# main.net
KiCad netlist of a schematic drawn in EAGLE
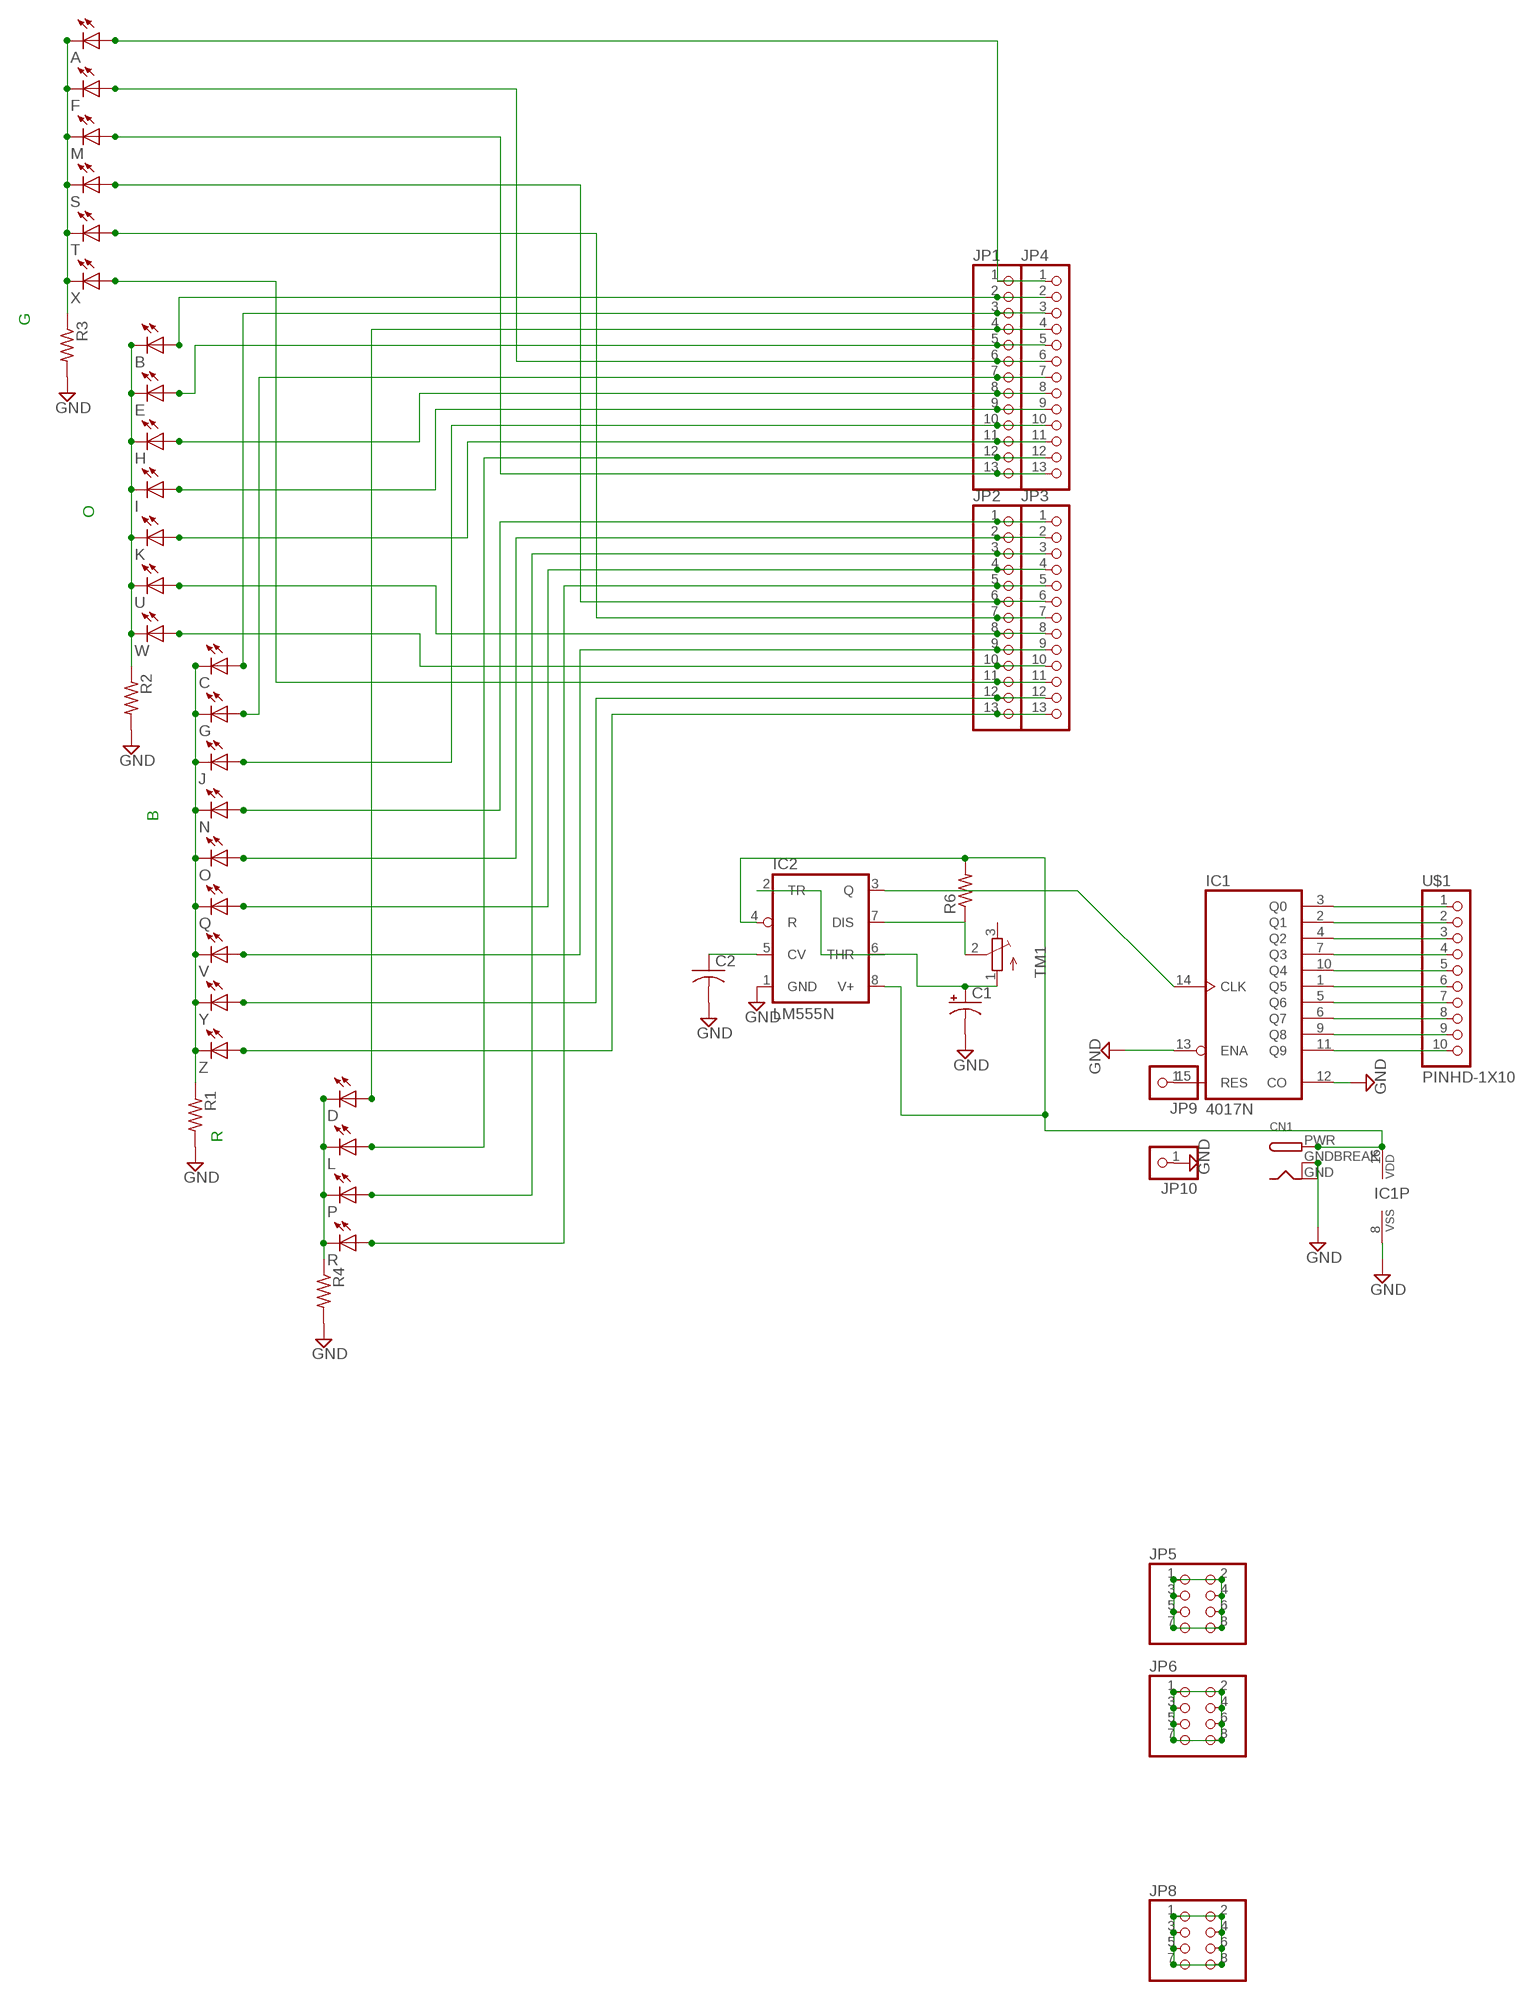
[diagram p0: schematic, sheet 1]

(export (version "E")
  (design (tool "Eeschema 10.0.6"))
  (components
    (comp (ref "A")
      (value "LED3MM")
      (footprint "eagle-import:LED3MM")
      (libsource (lib "eagle-import") (part "LED3MM"))
    )
    (comp (ref "B")
      (value "LED3MM")
      (footprint "eagle-import:LED3MM")
      (libsource (lib "eagle-import") (part "LED3MM"))
    )
    (comp (ref "C")
      (value "LED3MM")
      (footprint "eagle-import:LED3MM")
      (libsource (lib "eagle-import") (part "LED3MM"))
    )
    (comp (ref "C1")
      (value "CPOL-USE3.5-10")
      (footprint "eagle-import:E3,5-10")
      (libsource (lib "eagle-import") (part "CPOL-USE3.5-10"))
    )
    (comp (ref "C2")
      (value "C-US025-024X044")
      (footprint "eagle-import:C025-024X044")
      (libsource (lib "eagle-import") (part "C-US025-024X044"))
    )
    (comp (ref "CN1")
      (value "DCBARRELPTH")
      (footprint "eagle-import:DCJACK_2MM_PTH")
      (libsource (lib "eagle-import") (part "DCBARRELPTH"))
    )
    (comp (ref "D")
      (value "LED3MM")
      (footprint "eagle-import:LED3MM")
      (libsource (lib "eagle-import") (part "LED3MM"))
    )
    (comp (ref "E")
      (value "LED3MM")
      (footprint "eagle-import:LED3MM")
      (libsource (lib "eagle-import") (part "LED3MM"))
    )
    (comp (ref "F")
      (value "LED3MM")
      (footprint "eagle-import:LED3MM")
      (libsource (lib "eagle-import") (part "LED3MM"))
    )
    (comp (ref "G")
      (value "LED3MM")
      (footprint "eagle-import:LED3MM")
      (libsource (lib "eagle-import") (part "LED3MM"))
    )
    (comp (ref "H")
      (value "LED3MM")
      (footprint "eagle-import:LED3MM")
      (libsource (lib "eagle-import") (part "LED3MM"))
    )
    (comp (ref "I")
      (value "LED3MM")
      (footprint "eagle-import:LED3MM")
      (libsource (lib "eagle-import") (part "LED3MM"))
    )
    (comp (ref "IC1")
      (value "4017N")
      (footprint "eagle-import:DIL16")
      (libsource (lib "eagle-import") (part "4017N"))
    )
    (comp (ref "IC2")
      (value "LM555N")
      (footprint "eagle-import:DIL08")
      (libsource (lib "eagle-import") (part "555NLM"))
    )
    (comp (ref "J")
      (value "LED3MM")
      (footprint "eagle-import:LED3MM")
      (libsource (lib "eagle-import") (part "LED3MM"))
    )
    (comp (ref "JP1")
      (value "PINHD-1X13")
      (footprint "eagle-import:1X13")
      (libsource (lib "eagle-import") (part "PINHD-1X13"))
    )
    (comp (ref "JP2")
      (value "PINHD-1X13")
      (footprint "eagle-import:1X13")
      (libsource (lib "eagle-import") (part "PINHD-1X13"))
    )
    (comp (ref "JP3")
      (value "PINHD-1X13")
      (footprint "eagle-import:1X13")
      (libsource (lib "eagle-import") (part "PINHD-1X13"))
    )
    (comp (ref "JP4")
      (value "PINHD-1X13")
      (footprint "eagle-import:1X13")
      (libsource (lib "eagle-import") (part "PINHD-1X13"))
    )
    (comp (ref "JP5")
      (value "PINHD-2X4")
      (footprint "eagle-import:2X04")
      (libsource (lib "eagle-import") (part "PINHD-2X4"))
    )
    (comp (ref "JP6")
      (value "PINHD-2X4")
      (footprint "eagle-import:2X04")
      (libsource (lib "eagle-import") (part "PINHD-2X4"))
    )
    (comp (ref "JP8")
      (value "PINHD-2X4")
      (footprint "eagle-import:2X04")
      (libsource (lib "eagle-import") (part "PINHD-2X4"))
    )
    (comp (ref "JP9")
      (value "PINHD-1X1")
      (footprint "eagle-import:1X01")
      (libsource (lib "eagle-import") (part "PINHD-1X1"))
    )
    (comp (ref "JP10")
      (value "PINHD-1X1")
      (footprint "eagle-import:1X01")
      (libsource (lib "eagle-import") (part "PINHD-1X1"))
    )
    (comp (ref "K")
      (value "LED3MM")
      (footprint "eagle-import:LED3MM")
      (libsource (lib "eagle-import") (part "LED3MM"))
    )
    (comp (ref "L")
      (value "LED3MM")
      (footprint "eagle-import:LED3MM")
      (libsource (lib "eagle-import") (part "LED3MM"))
    )
    (comp (ref "M")
      (value "LED3MM")
      (footprint "eagle-import:LED3MM")
      (libsource (lib "eagle-import") (part "LED3MM"))
    )
    (comp (ref "N")
      (value "LED3MM")
      (footprint "eagle-import:LED3MM")
      (libsource (lib "eagle-import") (part "LED3MM"))
    )
    (comp (ref "O")
      (value "LED3MM")
      (footprint "eagle-import:LED3MM")
      (libsource (lib "eagle-import") (part "LED3MM"))
    )
    (comp (ref "P")
      (value "LED3MM")
      (footprint "eagle-import:LED3MM")
      (libsource (lib "eagle-import") (part "LED3MM"))
    )
    (comp (ref "Q")
      (value "LED3MM")
      (footprint "eagle-import:LED3MM")
      (libsource (lib "eagle-import") (part "LED3MM"))
    )
    (comp (ref "R")
      (value "LED3MM")
      (footprint "eagle-import:LED3MM")
      (libsource (lib "eagle-import") (part "LED3MM"))
    )
    (comp (ref "R1")
      (value "R-US_0207/7")
      (footprint "eagle-import:0207_7")
      (libsource (lib "eagle-import") (part "R-US_0207/7"))
    )
    (comp (ref "R2")
      (value "R-US_0207/7")
      (footprint "eagle-import:0207_7")
      (libsource (lib "eagle-import") (part "R-US_0207/7"))
    )
    (comp (ref "R3")
      (value "R-US_0207/7")
      (footprint "eagle-import:0207_7")
      (libsource (lib "eagle-import") (part "R-US_0207/7"))
    )
    (comp (ref "R4")
      (value "R-US_0207/7")
      (footprint "eagle-import:0207_7")
      (libsource (lib "eagle-import") (part "R-US_0207/7"))
    )
    (comp (ref "R6")
      (value "R-US_0207/7")
      (footprint "eagle-import:0207_7")
      (libsource (lib "eagle-import") (part "R-US_0207/7"))
    )
    (comp (ref "S")
      (value "LED3MM")
      (footprint "eagle-import:LED3MM")
      (libsource (lib "eagle-import") (part "LED3MM"))
    )
    (comp (ref "T")
      (value "LED3MM")
      (footprint "eagle-import:LED3MM")
      (libsource (lib "eagle-import") (part "LED3MM"))
    )
    (comp (ref "TM1")
      (value "TRIMPOT3386")
      (footprint "eagle-import:TRIM-3386")
      (libsource (lib "eagle-import") (part "TRIMPOT3386"))
    )
    (comp (ref "U")
      (value "LED3MM")
      (footprint "eagle-import:LED3MM")
      (libsource (lib "eagle-import") (part "LED3MM"))
    )
    (comp (ref "U$1")
      (value "PINHD-1X10")
      (footprint "eagle-import:1X10-BIG")
      (libsource (lib "eagle-import") (part "PINHD-1X10"))
    )
    (comp (ref "V")
      (value "LED3MM")
      (footprint "eagle-import:LED3MM")
      (libsource (lib "eagle-import") (part "LED3MM"))
    )
    (comp (ref "W")
      (value "LED3MM")
      (footprint "eagle-import:LED3MM")
      (libsource (lib "eagle-import") (part "LED3MM"))
    )
    (comp (ref "X")
      (value "LED3MM")
      (footprint "eagle-import:LED3MM")
      (libsource (lib "eagle-import") (part "LED3MM"))
    )
    (comp (ref "Y")
      (value "LED3MM")
      (footprint "eagle-import:LED3MM")
      (libsource (lib "eagle-import") (part "LED3MM"))
    )
    (comp (ref "Z")
      (value "LED3MM")
      (footprint "eagle-import:LED3MM")
      (libsource (lib "eagle-import") (part "LED3MM"))
    )
  )
  (nets
    (net (code "1") (name "GND") (class "Default")
      (node (ref "C1") (pin "-") (pinfunction "-_-") (pintype "passive"))
      (node (ref "C2") (pin "2") (pinfunction "2_2") (pintype "passive"))
      (node (ref "CN1") (pin "GND") (pinfunction "GND_GND") (pintype "power_in"))
      (node (ref "CN1") (pin "GNDBREAK") (pinfunction "GNDBREAK_GNDBREAK") (pintype "power_in"))
      (node (ref "IC1") (pin "12") (pinfunction "CO_12") (pintype "output"))
      (node (ref "IC1") (pin "13") (pinfunction "ENA_13") (pintype "input"))
      (node (ref "IC1") (pin "8") (pinfunction "VSS_8") (pintype "power_in"))
      (node (ref "IC2") (pin "1") (pinfunction "GND_1") (pintype "power_in"))
      (node (ref "JP10") (pin "1") (pinfunction "1_1") (pintype "passive"))
      (node (ref "R1") (pin "2") (pinfunction "2_2") (pintype "passive"))
      (node (ref "R2") (pin "2") (pinfunction "2_2") (pintype "passive"))
      (node (ref "R3") (pin "2") (pinfunction "2_2") (pintype "passive"))
      (node (ref "R4") (pin "2") (pinfunction "2_2") (pintype "passive"))
    )
    (net (code "2") (name "Net-(A-C)") (class "Default")
      (node (ref "A") (pin "K") (pinfunction "C_K") (pintype "passive"))
      (node (ref "F") (pin "K") (pinfunction "C_K") (pintype "passive"))
      (node (ref "M") (pin "K") (pinfunction "C_K") (pintype "passive"))
      (node (ref "R3") (pin "1") (pinfunction "1_1") (pintype "passive"))
      (node (ref "S") (pin "K") (pinfunction "C_K") (pintype "passive"))
      (node (ref "T") (pin "K") (pinfunction "C_K") (pintype "passive"))
      (node (ref "X") (pin "K") (pinfunction "C_K") (pintype "passive"))
    )
    (net (code "3") (name "Net-(A-PadA)") (class "Default")
      (node (ref "A") (pin "A") (pinfunction "A_A") (pintype "passive"))
      (node (ref "JP1") (pin "1") (pinfunction "1_1") (pintype "passive"))
      (node (ref "JP4") (pin "1") (pinfunction "1_1") (pintype "passive"))
    )
    (net (code "4") (name "Net-(B-C)") (class "Default")
      (node (ref "B") (pin "K") (pinfunction "C_K") (pintype "passive"))
      (node (ref "E") (pin "K") (pinfunction "C_K") (pintype "passive"))
      (node (ref "H") (pin "K") (pinfunction "C_K") (pintype "passive"))
      (node (ref "I") (pin "K") (pinfunction "C_K") (pintype "passive"))
      (node (ref "K") (pin "K") (pinfunction "C_K") (pintype "passive"))
      (node (ref "R2") (pin "1") (pinfunction "1_1") (pintype "passive"))
      (node (ref "U") (pin "K") (pinfunction "C_K") (pintype "passive"))
      (node (ref "W") (pin "K") (pinfunction "C_K") (pintype "passive"))
    )
    (net (code "5") (name "Net-(B-PadA)") (class "Default")
      (node (ref "B") (pin "A") (pinfunction "A_A") (pintype "passive"))
      (node (ref "JP1") (pin "2") (pinfunction "2_2") (pintype "passive"))
      (node (ref "JP4") (pin "2") (pinfunction "2_2") (pintype "passive"))
    )
    (net (code "6") (name "Net-(C-C)") (class "Default")
      (node (ref "C") (pin "K") (pinfunction "C_K") (pintype "passive"))
      (node (ref "G") (pin "K") (pinfunction "C_K") (pintype "passive"))
      (node (ref "J") (pin "K") (pinfunction "C_K") (pintype "passive"))
      (node (ref "N") (pin "K") (pinfunction "C_K") (pintype "passive"))
      (node (ref "O") (pin "K") (pinfunction "C_K") (pintype "passive"))
      (node (ref "Q") (pin "K") (pinfunction "C_K") (pintype "passive"))
      (node (ref "R1") (pin "1") (pinfunction "1_1") (pintype "passive"))
      (node (ref "V") (pin "K") (pinfunction "C_K") (pintype "passive"))
      (node (ref "Y") (pin "K") (pinfunction "C_K") (pintype "passive"))
      (node (ref "Z") (pin "K") (pinfunction "C_K") (pintype "passive"))
    )
    (net (code "7") (name "Net-(C-PadA)") (class "Default")
      (node (ref "C") (pin "A") (pinfunction "A_A") (pintype "passive"))
      (node (ref "JP1") (pin "3") (pinfunction "3_3") (pintype "passive"))
      (node (ref "JP4") (pin "3") (pinfunction "3_3") (pintype "passive"))
    )
    (net (code "8") (name "Net-(D-C)") (class "Default")
      (node (ref "D") (pin "K") (pinfunction "C_K") (pintype "passive"))
      (node (ref "L") (pin "K") (pinfunction "C_K") (pintype "passive"))
      (node (ref "P") (pin "K") (pinfunction "C_K") (pintype "passive"))
      (node (ref "R") (pin "K") (pinfunction "C_K") (pintype "passive"))
      (node (ref "R4") (pin "1") (pinfunction "1_1") (pintype "passive"))
    )
    (net (code "9") (name "Net-(D-PadA)") (class "Default")
      (node (ref "D") (pin "A") (pinfunction "A_A") (pintype "passive"))
      (node (ref "JP1") (pin "4") (pinfunction "4_4") (pintype "passive"))
      (node (ref "JP4") (pin "4") (pinfunction "4_4") (pintype "passive"))
    )
    (net (code "10") (name "Net-(E-PadA)") (class "Default")
      (node (ref "E") (pin "A") (pinfunction "A_A") (pintype "passive"))
      (node (ref "JP1") (pin "5") (pinfunction "5_5") (pintype "passive"))
      (node (ref "JP4") (pin "5") (pinfunction "5_5") (pintype "passive"))
    )
    (net (code "11") (name "Net-(F-PadA)") (class "Default")
      (node (ref "F") (pin "A") (pinfunction "A_A") (pintype "passive"))
      (node (ref "JP1") (pin "6") (pinfunction "6_6") (pintype "passive"))
      (node (ref "JP4") (pin "6") (pinfunction "6_6") (pintype "passive"))
    )
    (net (code "12") (name "Net-(G-PadA)") (class "Default")
      (node (ref "G") (pin "A") (pinfunction "A_A") (pintype "passive"))
      (node (ref "JP1") (pin "7") (pinfunction "7_7") (pintype "passive"))
      (node (ref "JP4") (pin "7") (pinfunction "7_7") (pintype "passive"))
    )
    (net (code "13") (name "Net-(H-PadA)") (class "Default")
      (node (ref "H") (pin "A") (pinfunction "A_A") (pintype "passive"))
      (node (ref "JP1") (pin "8") (pinfunction "8_8") (pintype "passive"))
      (node (ref "JP4") (pin "8") (pinfunction "8_8") (pintype "passive"))
    )
    (net (code "14") (name "Net-(I-PadA)") (class "Default")
      (node (ref "I") (pin "A") (pinfunction "A_A") (pintype "passive"))
      (node (ref "JP1") (pin "9") (pinfunction "9_9") (pintype "passive"))
      (node (ref "JP4") (pin "9") (pinfunction "9_9") (pintype "passive"))
    )
    (net (code "15") (name "Net-(IC1A-CLK)") (class "Default")
      (node (ref "IC1") (pin "14") (pinfunction "CLK_14") (pintype "input"))
      (node (ref "IC2") (pin "3") (pinfunction "Q_3") (pintype "output"))
    )
    (net (code "16") (name "Net-(IC1A-Q0)") (class "Default")
      (node (ref "IC1") (pin "3") (pinfunction "Q0_3") (pintype "output"))
      (node (ref "U$1") (pin "1") (pinfunction "1_1") (pintype "passive"))
    )
    (net (code "17") (name "Net-(IC1A-Q1)") (class "Default")
      (node (ref "IC1") (pin "2") (pinfunction "Q1_2") (pintype "output"))
      (node (ref "U$1") (pin "2") (pinfunction "2_2") (pintype "passive"))
    )
    (net (code "18") (name "Net-(IC1A-Q2)") (class "Default")
      (node (ref "IC1") (pin "4") (pinfunction "Q2_4") (pintype "output"))
      (node (ref "U$1") (pin "3") (pinfunction "3_3") (pintype "passive"))
    )
    (net (code "19") (name "Net-(IC1A-Q3)") (class "Default")
      (node (ref "IC1") (pin "7") (pinfunction "Q3_7") (pintype "output"))
      (node (ref "U$1") (pin "4") (pinfunction "4_4") (pintype "passive"))
    )
    (net (code "20") (name "Net-(IC1A-Q4)") (class "Default")
      (node (ref "IC1") (pin "10") (pinfunction "Q4_10") (pintype "output"))
      (node (ref "U$1") (pin "5") (pinfunction "5_5") (pintype "passive"))
    )
    (net (code "21") (name "Net-(IC1A-Q5)") (class "Default")
      (node (ref "IC1") (pin "1") (pinfunction "Q5_1") (pintype "output"))
      (node (ref "U$1") (pin "6") (pinfunction "6_6") (pintype "passive"))
    )
    (net (code "22") (name "Net-(IC1A-Q6)") (class "Default")
      (node (ref "IC1") (pin "5") (pinfunction "Q6_5") (pintype "output"))
      (node (ref "U$1") (pin "7") (pinfunction "7_7") (pintype "passive"))
    )
    (net (code "23") (name "Net-(IC1A-Q7)") (class "Default")
      (node (ref "IC1") (pin "6") (pinfunction "Q7_6") (pintype "output"))
      (node (ref "U$1") (pin "8") (pinfunction "8_8") (pintype "passive"))
    )
    (net (code "24") (name "Net-(IC1A-Q8)") (class "Default")
      (node (ref "IC1") (pin "9") (pinfunction "Q8_9") (pintype "output"))
      (node (ref "U$1") (pin "9") (pinfunction "9_9") (pintype "passive"))
    )
    (net (code "25") (name "Net-(IC1A-Q9)") (class "Default")
      (node (ref "IC1") (pin "11") (pinfunction "Q9_11") (pintype "output"))
      (node (ref "U$1") (pin "10") (pinfunction "10_10") (pintype "passive"))
    )
    (net (code "26") (name "Net-(IC1A-RES)") (class "Default")
      (node (ref "IC1") (pin "15") (pinfunction "RES_15") (pintype "input"))
      (node (ref "JP9") (pin "1") (pinfunction "1_1") (pintype "passive"))
    )
    (net (code "27") (name "Net-(IC1B-VDD)") (class "Default")
      (node (ref "CN1") (pin "PWR") (pinfunction "PWR_PWR") (pintype "power_in"))
      (node (ref "IC1") (pin "16") (pinfunction "VDD_16") (pintype "power_in"))
      (node (ref "IC2") (pin "4") (pinfunction "R_4") (pintype "input"))
      (node (ref "IC2") (pin "8") (pinfunction "V+_8") (pintype "power_in"))
      (node (ref "R6") (pin "2") (pinfunction "2_2") (pintype "passive"))
    )
    (net (code "28") (name "Net-(IC2-CV)") (class "Default")
      (node (ref "C2") (pin "1") (pinfunction "1_1") (pintype "passive"))
      (node (ref "IC2") (pin "5") (pinfunction "CV_5") (pintype "input"))
    )
    (net (code "29") (name "Net-(IC2-DIS)") (class "Default")
      (node (ref "IC2") (pin "7") (pinfunction "DIS_7") (pintype "input"))
      (node (ref "R6") (pin "1") (pinfunction "1_1") (pintype "passive"))
      (node (ref "TM1") (pin "2") (pinfunction "S_2") (pintype "passive"))
    )
    (net (code "30") (name "Net-(IC2-THR)") (class "Default")
      (node (ref "C1") (pin "+") (pinfunction "+_+") (pintype "passive"))
      (node (ref "IC2") (pin "2") (pinfunction "TR_2") (pintype "input"))
      (node (ref "IC2") (pin "6") (pinfunction "THR_6") (pintype "input"))
      (node (ref "TM1") (pin "1") (pinfunction "A_1") (pintype "passive"))
    )
    (net (code "31") (name "Net-(J-PadA)") (class "Default")
      (node (ref "J") (pin "A") (pinfunction "A_A") (pintype "passive"))
      (node (ref "JP1") (pin "10") (pinfunction "10_10") (pintype "passive"))
      (node (ref "JP4") (pin "10") (pinfunction "10_10") (pintype "passive"))
    )
    (net (code "32") (name "Net-(JP1-Pad11)") (class "Default")
      (node (ref "JP1") (pin "11") (pinfunction "11_11") (pintype "passive"))
      (node (ref "JP4") (pin "11") (pinfunction "11_11") (pintype "passive"))
      (node (ref "K") (pin "A") (pinfunction "A_A") (pintype "passive"))
    )
    (net (code "33") (name "Net-(JP1-Pad12)") (class "Default")
      (node (ref "JP1") (pin "12") (pinfunction "12_12") (pintype "passive"))
      (node (ref "JP4") (pin "12") (pinfunction "12_12") (pintype "passive"))
      (node (ref "L") (pin "A") (pinfunction "A_A") (pintype "passive"))
    )
    (net (code "34") (name "Net-(JP1-Pad13)") (class "Default")
      (node (ref "JP1") (pin "13") (pinfunction "13_13") (pintype "passive"))
      (node (ref "JP4") (pin "13") (pinfunction "13_13") (pintype "passive"))
      (node (ref "M") (pin "A") (pinfunction "A_A") (pintype "passive"))
    )
    (net (code "35") (name "Net-(JP2-Pad1)") (class "Default")
      (node (ref "JP2") (pin "1") (pinfunction "1_1") (pintype "passive"))
      (node (ref "JP3") (pin "1") (pinfunction "1_1") (pintype "passive"))
      (node (ref "N") (pin "A") (pinfunction "A_A") (pintype "passive"))
    )
    (net (code "36") (name "Net-(JP2-Pad2)") (class "Default")
      (node (ref "JP2") (pin "2") (pinfunction "2_2") (pintype "passive"))
      (node (ref "JP3") (pin "2") (pinfunction "2_2") (pintype "passive"))
      (node (ref "O") (pin "A") (pinfunction "A_A") (pintype "passive"))
    )
    (net (code "37") (name "Net-(JP2-Pad3)") (class "Default")
      (node (ref "JP2") (pin "3") (pinfunction "3_3") (pintype "passive"))
      (node (ref "JP3") (pin "3") (pinfunction "3_3") (pintype "passive"))
      (node (ref "P") (pin "A") (pinfunction "A_A") (pintype "passive"))
    )
    (net (code "38") (name "Net-(JP2-Pad4)") (class "Default")
      (node (ref "JP2") (pin "4") (pinfunction "4_4") (pintype "passive"))
      (node (ref "JP3") (pin "4") (pinfunction "4_4") (pintype "passive"))
      (node (ref "Q") (pin "A") (pinfunction "A_A") (pintype "passive"))
    )
    (net (code "39") (name "Net-(JP2-Pad5)") (class "Default")
      (node (ref "JP2") (pin "5") (pinfunction "5_5") (pintype "passive"))
      (node (ref "JP3") (pin "5") (pinfunction "5_5") (pintype "passive"))
      (node (ref "R") (pin "A") (pinfunction "A_A") (pintype "passive"))
    )
    (net (code "40") (name "Net-(JP2-Pad6)") (class "Default")
      (node (ref "JP2") (pin "6") (pinfunction "6_6") (pintype "passive"))
      (node (ref "JP3") (pin "6") (pinfunction "6_6") (pintype "passive"))
      (node (ref "S") (pin "A") (pinfunction "A_A") (pintype "passive"))
    )
    (net (code "41") (name "Net-(JP2-Pad7)") (class "Default")
      (node (ref "JP2") (pin "7") (pinfunction "7_7") (pintype "passive"))
      (node (ref "JP3") (pin "7") (pinfunction "7_7") (pintype "passive"))
      (node (ref "T") (pin "A") (pinfunction "A_A") (pintype "passive"))
    )
    (net (code "42") (name "Net-(JP2-Pad8)") (class "Default")
      (node (ref "JP2") (pin "8") (pinfunction "8_8") (pintype "passive"))
      (node (ref "JP3") (pin "8") (pinfunction "8_8") (pintype "passive"))
      (node (ref "U") (pin "A") (pinfunction "A_A") (pintype "passive"))
    )
    (net (code "43") (name "Net-(JP2-Pad9)") (class "Default")
      (node (ref "JP2") (pin "9") (pinfunction "9_9") (pintype "passive"))
      (node (ref "JP3") (pin "9") (pinfunction "9_9") (pintype "passive"))
      (node (ref "V") (pin "A") (pinfunction "A_A") (pintype "passive"))
    )
    (net (code "44") (name "Net-(JP2-Pad10)") (class "Default")
      (node (ref "JP2") (pin "10") (pinfunction "10_10") (pintype "passive"))
      (node (ref "JP3") (pin "10") (pinfunction "10_10") (pintype "passive"))
      (node (ref "W") (pin "A") (pinfunction "A_A") (pintype "passive"))
    )
    (net (code "45") (name "Net-(JP2-Pad11)") (class "Default")
      (node (ref "JP2") (pin "11") (pinfunction "11_11") (pintype "passive"))
      (node (ref "JP3") (pin "11") (pinfunction "11_11") (pintype "passive"))
      (node (ref "X") (pin "A") (pinfunction "A_A") (pintype "passive"))
    )
    (net (code "46") (name "Net-(JP2-Pad12)") (class "Default")
      (node (ref "JP2") (pin "12") (pinfunction "12_12") (pintype "passive"))
      (node (ref "JP3") (pin "12") (pinfunction "12_12") (pintype "passive"))
      (node (ref "Y") (pin "A") (pinfunction "A_A") (pintype "passive"))
    )
    (net (code "47") (name "Net-(JP2-Pad13)") (class "Default")
      (node (ref "JP2") (pin "13") (pinfunction "13_13") (pintype "passive"))
      (node (ref "JP3") (pin "13") (pinfunction "13_13") (pintype "passive"))
      (node (ref "Z") (pin "A") (pinfunction "A_A") (pintype "passive"))
    )
    (net (code "48") (name "Net-(JP5-Pad1)") (class "Default")
      (node (ref "JP5") (pin "1") (pinfunction "1_1") (pintype "passive"))
      (node (ref "JP5") (pin "2") (pinfunction "2_2") (pintype "passive"))
      (node (ref "JP5") (pin "3") (pinfunction "3_3") (pintype "passive"))
      (node (ref "JP5") (pin "4") (pinfunction "4_4") (pintype "passive"))
      (node (ref "JP5") (pin "5") (pinfunction "5_5") (pintype "passive"))
      (node (ref "JP5") (pin "6") (pinfunction "6_6") (pintype "passive"))
      (node (ref "JP5") (pin "7") (pinfunction "7_7") (pintype "passive"))
      (node (ref "JP5") (pin "8") (pinfunction "8_8") (pintype "passive"))
    )
    (net (code "49") (name "Net-(JP6-Pad1)") (class "Default")
      (node (ref "JP6") (pin "1") (pinfunction "1_1") (pintype "passive"))
      (node (ref "JP6") (pin "2") (pinfunction "2_2") (pintype "passive"))
      (node (ref "JP6") (pin "3") (pinfunction "3_3") (pintype "passive"))
      (node (ref "JP6") (pin "4") (pinfunction "4_4") (pintype "passive"))
      (node (ref "JP6") (pin "5") (pinfunction "5_5") (pintype "passive"))
      (node (ref "JP6") (pin "6") (pinfunction "6_6") (pintype "passive"))
      (node (ref "JP6") (pin "7") (pinfunction "7_7") (pintype "passive"))
      (node (ref "JP6") (pin "8") (pinfunction "8_8") (pintype "passive"))
    )
    (net (code "50") (name "Net-(JP8-Pad1)") (class "Default")
      (node (ref "JP8") (pin "1") (pinfunction "1_1") (pintype "passive"))
      (node (ref "JP8") (pin "2") (pinfunction "2_2") (pintype "passive"))
      (node (ref "JP8") (pin "3") (pinfunction "3_3") (pintype "passive"))
      (node (ref "JP8") (pin "4") (pinfunction "4_4") (pintype "passive"))
      (node (ref "JP8") (pin "5") (pinfunction "5_5") (pintype "passive"))
      (node (ref "JP8") (pin "6") (pinfunction "6_6") (pintype "passive"))
      (node (ref "JP8") (pin "7") (pinfunction "7_7") (pintype "passive"))
      (node (ref "JP8") (pin "8") (pinfunction "8_8") (pintype "passive"))
    )
    (net (code "51") (name "unconnected-(TM1-E-Pad3)") (class "Default")
      (node (ref "TM1") (pin "3") (pinfunction "E_3") (pintype "passive"))
    )
  )
)
